# Schematic.net
KiCad netlist of a schematic drawn in Altium Designer
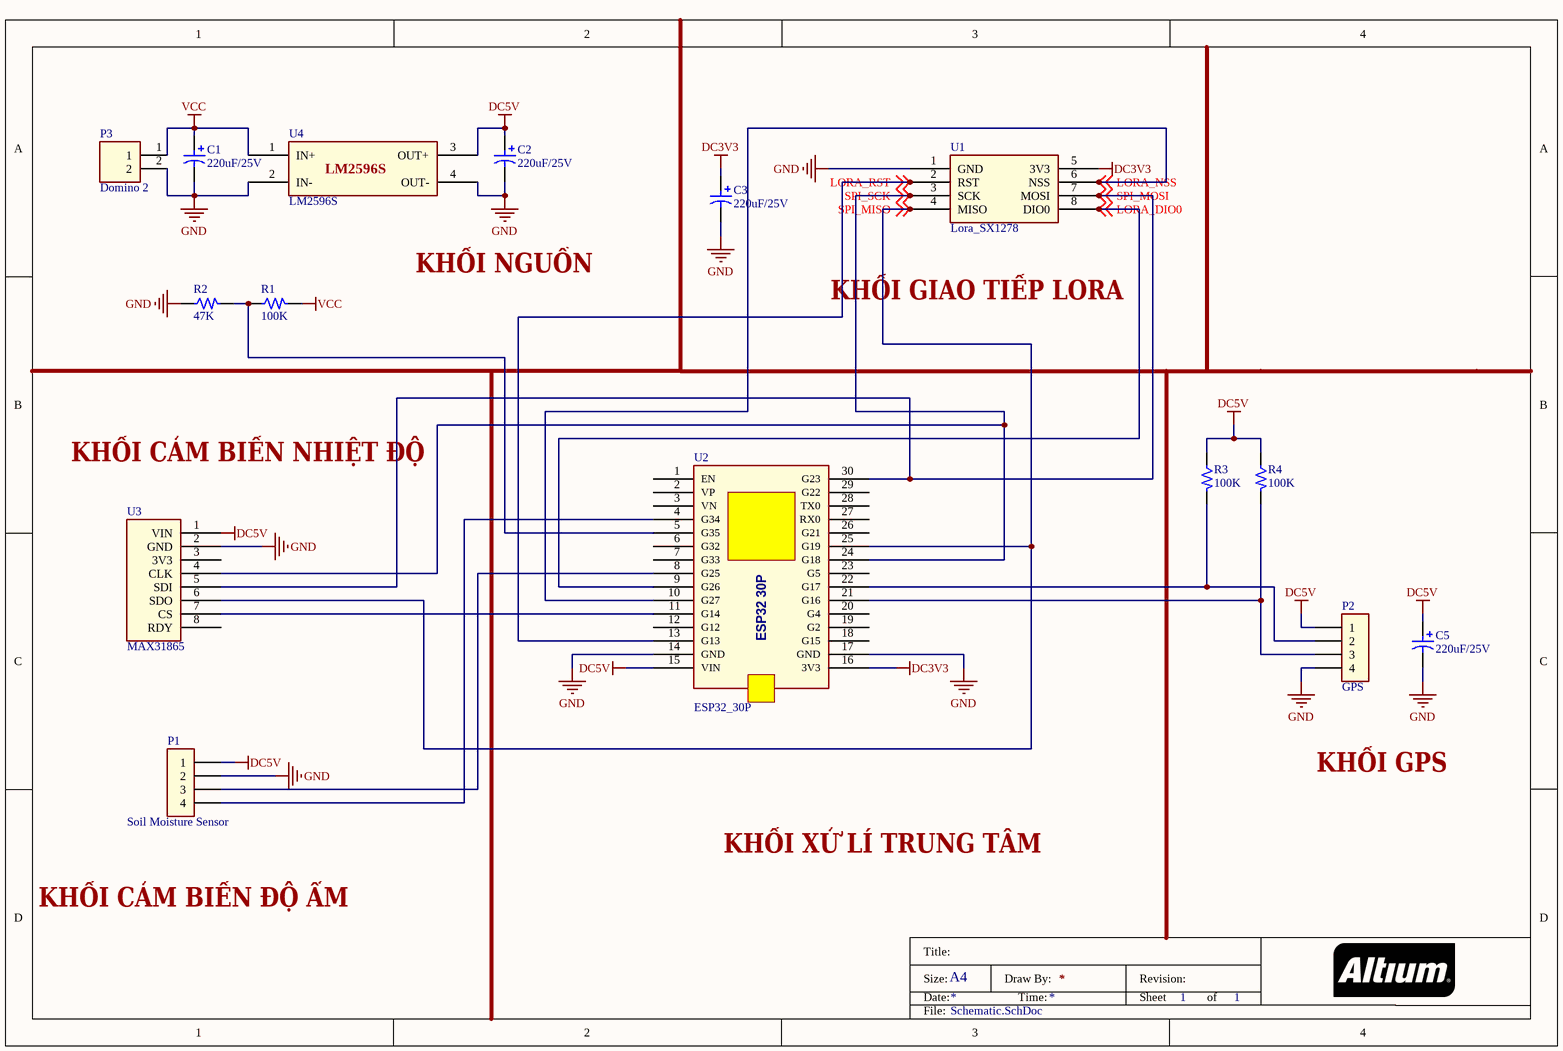
[diagram p0: Schematic.SchDoc]

(export (version "E")
  (design (tool "Eeschema 10.0.6"))
  (components
    (comp (ref "C1")
      (value "220uF/25V")
      (footprint "CAP-ALUM-10x12.5")
      (description "Capacitor Aluminum 220uF 20% 25V Radial")
      (fields (field (name "MPN") "CLA4514"))
      (libsource (lib "SachTranLib") (part "EEUTA1E221"))
    )
    (comp (ref "C2")
      (value "220uF/25V")
      (footprint "CAP-ALUM-10x12.5")
      (description "Capacitor Aluminum 220uF 20% 25V Radial")
      (fields (field (name "MPN") "CLA4514"))
      (libsource (lib "SachTranLib") (part "EEUTA1E221"))
    )
    (comp (ref "C3")
      (value "220uF/25V")
      (footprint "CAP-ALUM-10x12.5")
      (description "Capacitor Aluminum 220uF 20% 25V Radial")
      (fields (field (name "MPN") "CLA4514"))
      (libsource (lib "SachTranLib") (part "EEUTA1E221"))
    )
    (comp (ref "C5")
      (value "220uF/25V")
      (footprint "CAP-ALUM-10x12.5")
      (description "Capacitor Aluminum 220uF 20% 25V Radial")
      (fields (field (name "MPN") "CLA4514"))
      (libsource (lib "SachTranLib") (part "EEUTA1E221"))
    )
    (comp (ref "P1")
      (value "Soil Moisture Sensor")
      (footprint "B4B-XH-A")
      (description "Connector Header Through Hole 4 position 0.098\" (2.50mm)")
      (libsource (lib "") (part "B4B-XH-A_1"))
    )
    (comp (ref "P2")
      (value "GPS")
      (footprint "B4B-XH-A")
      (description "Connector Header Through Hole 4 position 0.098\" (2.50mm)")
      (libsource (lib "SachTranLib") (part "B4B-XH-A"))
    )
    (comp (ref "P3")
      (value "Domino 2")
      (footprint "Domino-2")
      (libsource (lib "SachTranLib") (part "Domino-2"))
    )
    (comp (ref "R1")
      (value "100K")
      (footprint "R1/4W-H1")
      (description "Resistor 1/4W Through Hole")
      (libsource (lib "SachTranLib") (part "RES-1/4W"))
    )
    (comp (ref "R2")
      (value "47K")
      (footprint "R1/4W-H1")
      (description "Resistor 1/4W Through Hole")
      (libsource (lib "SachTranLib") (part "RES-1/4W"))
    )
    (comp (ref "R3")
      (value "100K")
      (footprint "R1/4W-H1")
      (description "Resistor 1/4W Through Hole")
      (libsource (lib "SachTranLib") (part "RES-1/4W"))
    )
    (comp (ref "R4")
      (value "100K")
      (footprint "R1/4W-H1")
      (description "Resistor 1/4W Through Hole")
      (libsource (lib "SachTranLib") (part "RES-1/4W"))
    )
    (comp (ref "U1")
      (value "Lora_SX1278")
      (footprint "Module-LORA-SX1278")
      (description "Module Lora SX1278 RA02 SPI")
      (libsource (lib "SachTranLib") (part "Module-Lora-SX1278-SPI"))
    )
    (comp (ref "U2")
      (value "ESP32_30P")
      (footprint "Kit-ESP32-30P")
      (description "Kit ESP32 30P")
      (libsource (lib "SachTranLib") (part "Kit_ESP32_30P"))
    )
    (comp (ref "U3")
      (value "MAX31865")
      (footprint "MODULE-MAX31865")
      (description "Module Max31865")
      (libsource (lib "SachTranLib") (part "Module-MAX31865"))
    )
    (comp (ref "U4")
      (value "LM2596S")
      (footprint "Module-LM2596S")
      (description "Module LM2596S")
      (libsource (lib "SachTranLib") (part "Module-LM2596S"))
    )
  )
  (nets
    (net (code "1") (name "DC3V3") (class "Default")
      (node (ref "C3") (pin "1") (pinfunction "1_1") (pintype "passive"))
      (node (ref "U1") (pin "5") (pinfunction "3V3_5") (pintype "passive"))
      (node (ref "U2") (pin "16") (pinfunction "3V3_16") (pintype "passive"))
    )
    (net (code "2") (name "DC5V") (class "Default")
      (node (ref "C2") (pin "1") (pinfunction "1_1") (pintype "passive"))
      (node (ref "C5") (pin "1") (pinfunction "1_1") (pintype "passive"))
      (node (ref "P1") (pin "1") (pinfunction "1_1") (pintype "passive"))
      (node (ref "P2") (pin "1") (pinfunction "1_1") (pintype "passive"))
      (node (ref "R3") (pin "1") (pinfunction "1_1") (pintype "passive"))
      (node (ref "R4") (pin "1") (pinfunction "1_1") (pintype "passive"))
      (node (ref "U2") (pin "15") (pinfunction "VIN_15") (pintype "passive"))
      (node (ref "U3") (pin "1") (pinfunction "VIN_1") (pintype "passive"))
      (node (ref "U4") (pin "3") (pinfunction "OUT+_3") (pintype "passive"))
    )
    (net (code "3") (name "GND") (class "Default")
      (node (ref "C1") (pin "2") (pinfunction "2_2") (pintype "passive"))
      (node (ref "C2") (pin "2") (pinfunction "2_2") (pintype "passive"))
      (node (ref "C3") (pin "2") (pinfunction "2_2") (pintype "passive"))
      (node (ref "C5") (pin "2") (pinfunction "2_2") (pintype "passive"))
      (node (ref "P1") (pin "2") (pinfunction "2_2") (pintype "passive"))
      (node (ref "P2") (pin "4") (pinfunction "4_4") (pintype "passive"))
      (node (ref "P3") (pin "2") (pinfunction "_2_2") (pintype "passive"))
      (node (ref "R2") (pin "1") (pinfunction "1_1") (pintype "passive"))
      (node (ref "U1") (pin "1") (pinfunction "GND_1") (pintype "passive"))
      (node (ref "U2") (pin "14") (pinfunction "GND_14") (pintype "passive"))
      (node (ref "U2") (pin "17") (pinfunction "GND_17") (pintype "passive"))
      (node (ref "U3") (pin "2") (pinfunction "GND_2") (pintype "passive"))
      (node (ref "U4") (pin "2") (pinfunction "IN-_2") (pintype "passive"))
      (node (ref "U4") (pin "4") (pinfunction "OUT-_4") (pintype "passive"))
    )
    (net (code "4") (name "LORA_DIO0") (class "Default")
      (node (ref "U1") (pin "8") (pinfunction "DIO0_8") (pintype "passive"))
      (node (ref "U2") (pin "9") (pinfunction "G26_9") (pintype "passive"))
    )
    (net (code "5") (name "LORA_NSS") (class "Default")
      (node (ref "U1") (pin "6") (pinfunction "NSS_6") (pintype "passive"))
      (node (ref "U2") (pin "10") (pinfunction "G27_10") (pintype "passive"))
    )
    (net (code "6") (name "LORA_RST") (class "Default")
      (node (ref "U1") (pin "2") (pinfunction "RST_2") (pintype "passive"))
      (node (ref "U2") (pin "13") (pinfunction "G13_13") (pintype "passive"))
    )
    (net (code "7") (name "Net-(U2-G14)") (class "Default")
      (node (ref "U2") (pin "11") (pinfunction "G14_11") (pintype "passive"))
      (node (ref "U3") (pin "7") (pinfunction "CS_7") (pintype "passive"))
    )
    (net (code "8") (name "Net-(U2-G16)") (class "Default")
      (node (ref "P2") (pin "3") (pinfunction "3_3") (pintype "passive"))
      (node (ref "R4") (pin "2") (pinfunction "2_2") (pintype "passive"))
      (node (ref "U2") (pin "21") (pinfunction "G16_21") (pintype "passive"))
    )
    (net (code "9") (name "Net-(U2-G17)") (class "Default")
      (node (ref "P2") (pin "2") (pinfunction "2_2") (pintype "passive"))
      (node (ref "R3") (pin "2") (pinfunction "2_2") (pintype "passive"))
      (node (ref "U2") (pin "22") (pinfunction "G17_22") (pintype "passive"))
    )
    (net (code "10") (name "Net-(U2-G25)") (class "Default")
      (node (ref "P1") (pin "3") (pinfunction "3_3") (pintype "passive"))
      (node (ref "U2") (pin "8") (pinfunction "G25_8") (pintype "passive"))
    )
    (net (code "11") (name "Net-(U2-G34)") (class "Default")
      (node (ref "P1") (pin "4") (pinfunction "4_4") (pintype "passive"))
      (node (ref "U2") (pin "4") (pinfunction "G34_4") (pintype "passive"))
    )
    (net (code "12") (name "Net-(U2-G35)") (class "Default")
      (node (ref "R1") (pin "1") (pinfunction "1_1") (pintype "passive"))
      (node (ref "R2") (pin "2") (pinfunction "2_2") (pintype "passive"))
      (node (ref "U2") (pin "5") (pinfunction "G35_5") (pintype "passive"))
    )
    (net (code "13") (name "SPI_MISO") (class "Default")
      (node (ref "U1") (pin "4") (pinfunction "MISO_4") (pintype "passive"))
      (node (ref "U2") (pin "25") (pinfunction "G19_25") (pintype "passive"))
      (node (ref "U3") (pin "6") (pinfunction "SDO_6") (pintype "passive"))
    )
    (net (code "14") (name "SPI_MOSI") (class "Default")
      (node (ref "U1") (pin "7") (pinfunction "MOSI_7") (pintype "passive"))
      (node (ref "U2") (pin "30") (pinfunction "G23_30") (pintype "passive"))
      (node (ref "U3") (pin "5") (pinfunction "SDI_5") (pintype "passive"))
    )
    (net (code "15") (name "SPI_SCK") (class "Default")
      (node (ref "U1") (pin "3") (pinfunction "SCK_3") (pintype "passive"))
      (node (ref "U2") (pin "24") (pinfunction "G18_24") (pintype "passive"))
      (node (ref "U3") (pin "4") (pinfunction "CLK_4") (pintype "passive"))
    )
    (net (code "16") (name "VCC") (class "Default")
      (node (ref "C1") (pin "1") (pinfunction "1_1") (pintype "passive"))
      (node (ref "P3") (pin "1") (pinfunction "1_1") (pintype "passive"))
      (node (ref "R1") (pin "2") (pinfunction "2_2") (pintype "passive"))
      (node (ref "U4") (pin "1") (pinfunction "IN+_1") (pintype "passive"))
    )
    (net (code "17") (name "unconnected-(U2-EN-Pad1)") (class "Default")
      (node (ref "U2") (pin "1") (pinfunction "EN_1") (pintype "passive"))
    )
    (net (code "18") (name "unconnected-(U2-G2-Pad19)") (class "Default")
      (node (ref "U2") (pin "19") (pinfunction "G2_19") (pintype "passive"))
    )
    (net (code "19") (name "unconnected-(U2-G4-Pad20)") (class "Default")
      (node (ref "U2") (pin "20") (pinfunction "G4_20") (pintype "passive"))
    )
    (net (code "20") (name "unconnected-(U2-G5-Pad23)") (class "Default")
      (node (ref "U2") (pin "23") (pinfunction "G5_23") (pintype "passive"))
    )
    (net (code "21") (name "unconnected-(U2-G12-Pad12)") (class "Default")
      (node (ref "U2") (pin "12") (pinfunction "G12_12") (pintype "passive"))
    )
    (net (code "22") (name "unconnected-(U2-G15-Pad18)") (class "Default")
      (node (ref "U2") (pin "18") (pinfunction "G15_18") (pintype "passive"))
    )
    (net (code "23") (name "unconnected-(U2-G21-Pad26)") (class "Default")
      (node (ref "U2") (pin "26") (pinfunction "G21_26") (pintype "passive"))
    )
    (net (code "24") (name "unconnected-(U2-G22-Pad29)") (class "Default")
      (node (ref "U2") (pin "29") (pinfunction "G22_29") (pintype "passive"))
    )
    (net (code "25") (name "unconnected-(U2-G32-Pad6)") (class "Default")
      (node (ref "U2") (pin "6") (pinfunction "G32_6") (pintype "passive"))
    )
    (net (code "26") (name "unconnected-(U2-G33-Pad7)") (class "Default")
      (node (ref "U2") (pin "7") (pinfunction "G33_7") (pintype "passive"))
    )
    (net (code "27") (name "unconnected-(U2-RX0-Pad27)") (class "Default")
      (node (ref "U2") (pin "27") (pinfunction "RX0_27") (pintype "passive"))
    )
    (net (code "28") (name "unconnected-(U2-TX0-Pad28)") (class "Default")
      (node (ref "U2") (pin "28") (pinfunction "TX0_28") (pintype "passive"))
    )
    (net (code "29") (name "unconnected-(U2-VN-Pad3)") (class "Default")
      (node (ref "U2") (pin "3") (pinfunction "VN_3") (pintype "passive"))
    )
    (net (code "30") (name "unconnected-(U2-VP-Pad2)") (class "Default")
      (node (ref "U2") (pin "2") (pinfunction "VP_2") (pintype "passive"))
    )
    (net (code "31") (name "unconnected-(U3-3V3-Pad3)") (class "Default")
      (node (ref "U3") (pin "3") (pinfunction "3V3_3") (pintype "passive"))
    )
    (net (code "32") (name "unconnected-(U3-RDY-Pad8)") (class "Default")
      (node (ref "U3") (pin "8") (pinfunction "RDY_8") (pintype "passive"))
    )
  )
)
